# dynext_v1_0.net
KiCad netlist of a schematic drawn in EAGLE
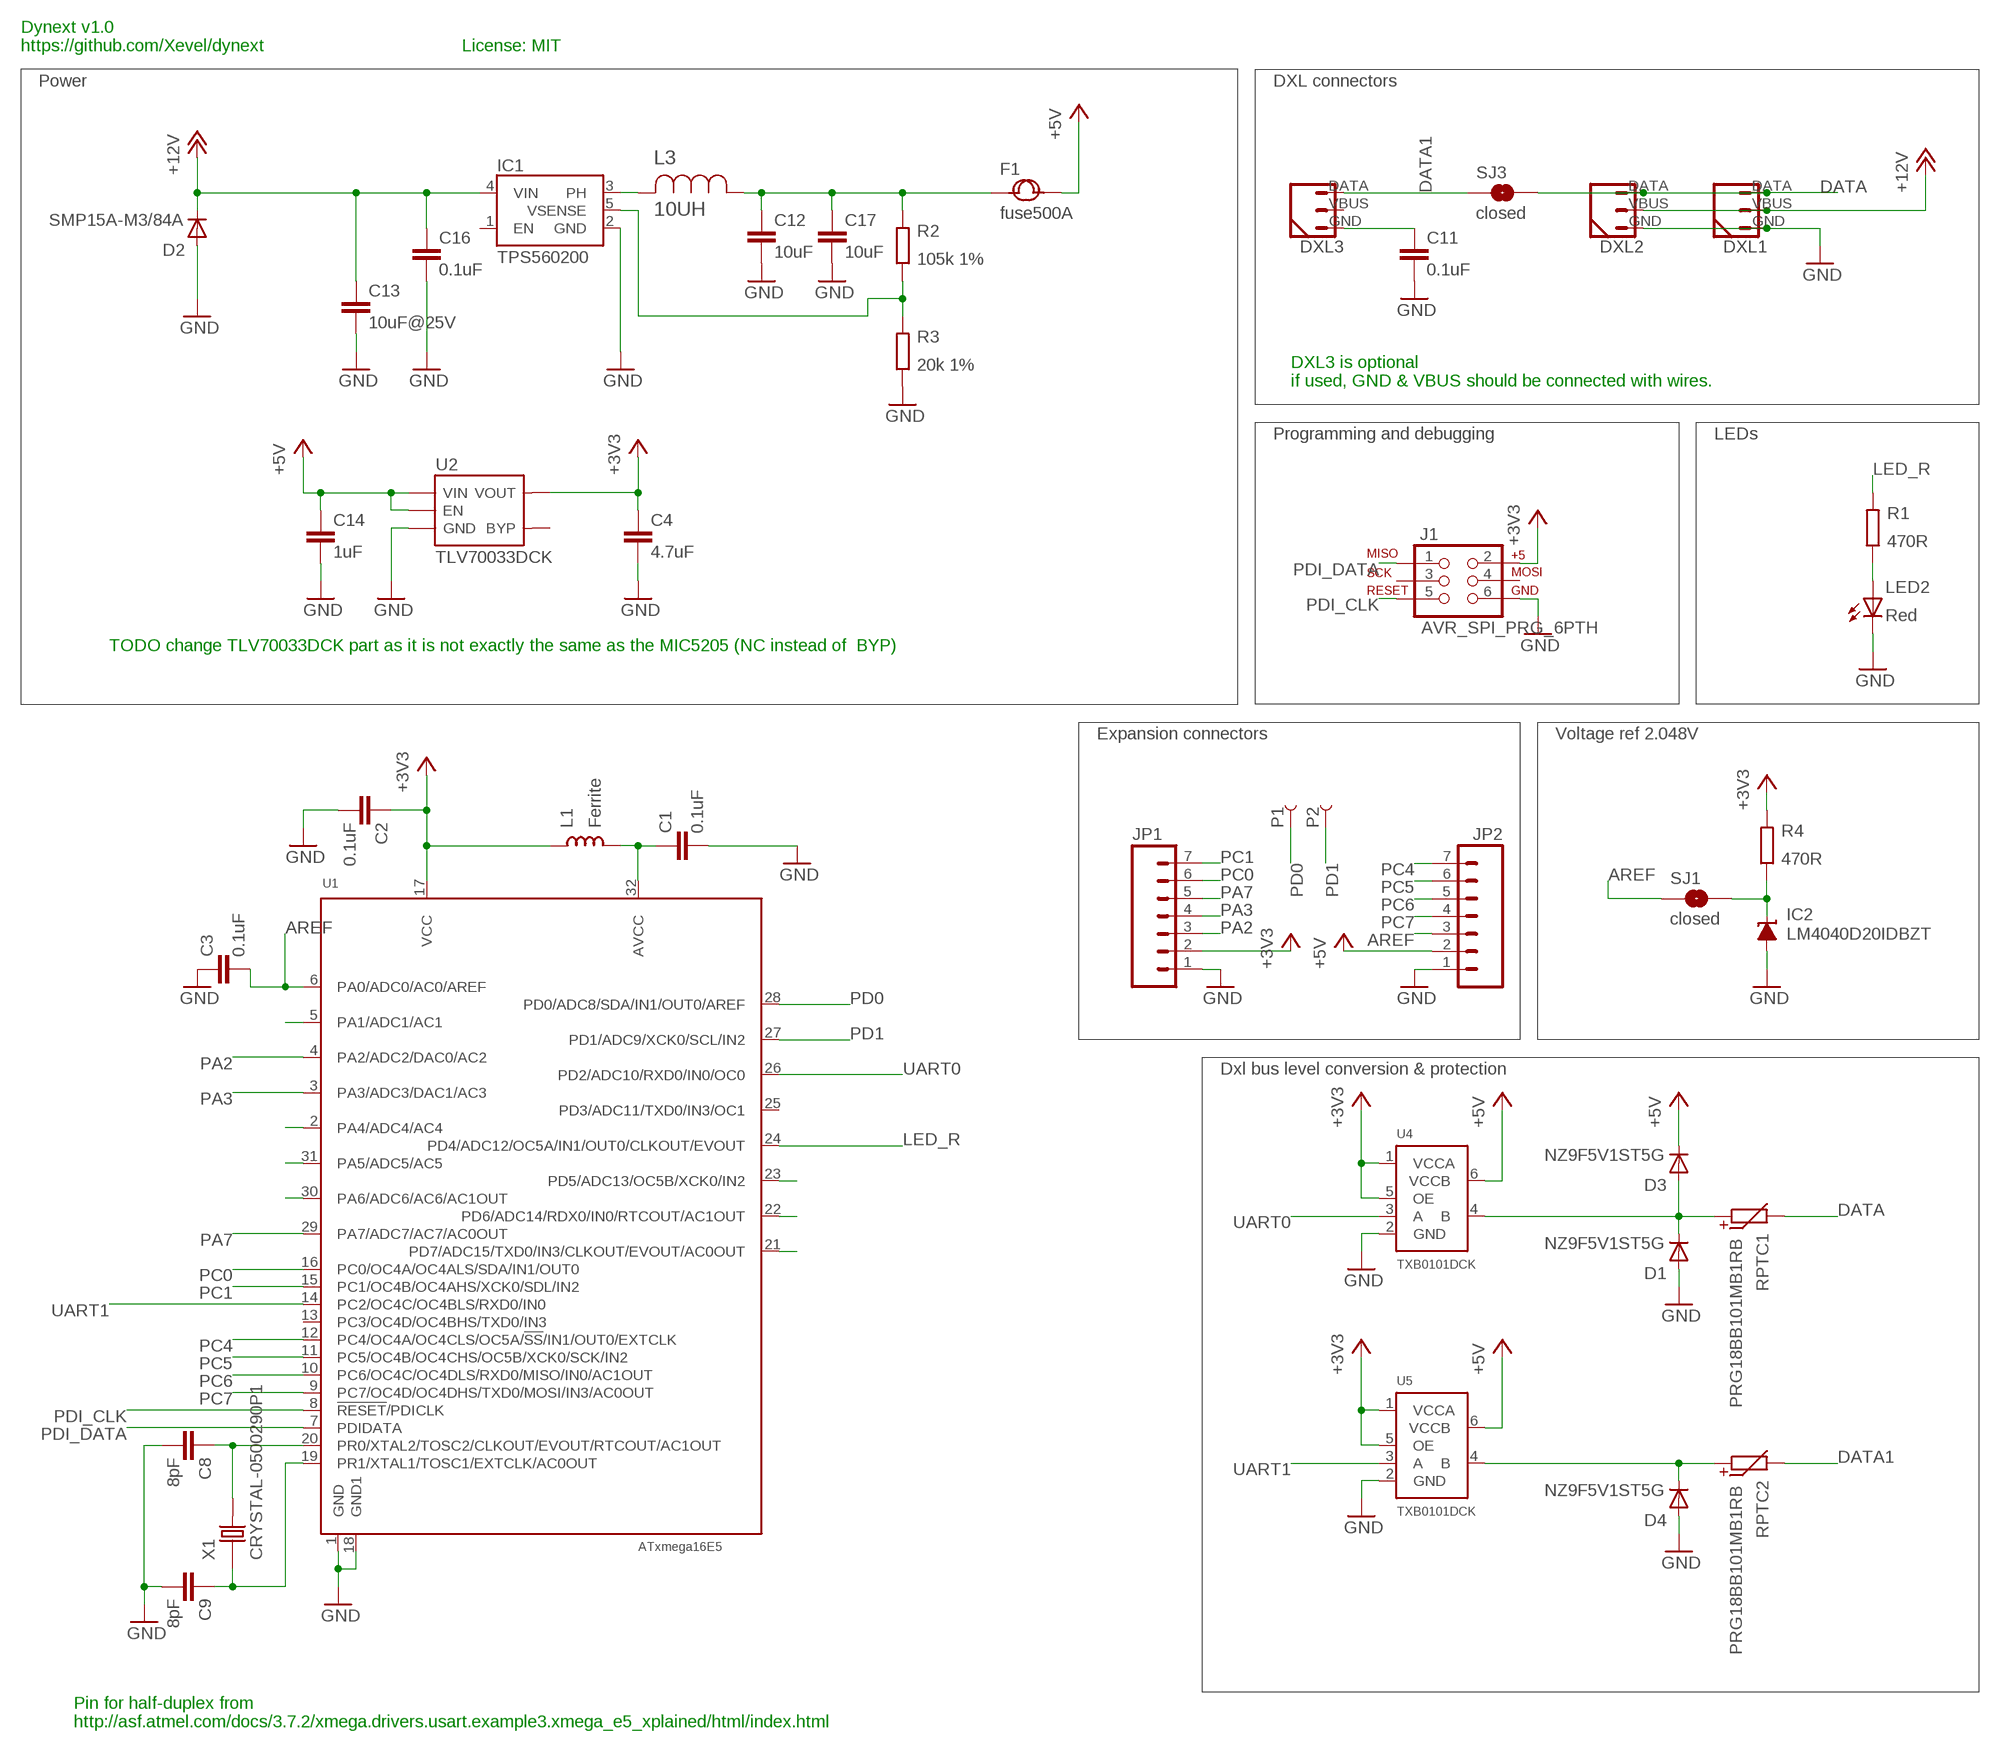
[diagram p0: schematic, sheet 1]

(export (version "E")
  (design (tool "Eeschema 10.0.6"))
  (components
    (comp (ref "C1")
      (value "0.1uF")
      (footprint "eagle-import:0402_N")
      (libsource (lib "eagle-import") (part "C0402"))
    )
    (comp (ref "C2")
      (value "0.1uF")
      (footprint "eagle-import:0402_N")
      (libsource (lib "eagle-import") (part "C0402"))
    )
    (comp (ref "C3")
      (value "0.1uF")
      (footprint "eagle-import:0402_N")
      (libsource (lib "eagle-import") (part "C0402"))
    )
    (comp (ref "C4")
      (value "4.7uF")
      (footprint "eagle-import:0603_N")
      (libsource (lib "eagle-import") (part "C0603"))
    )
    (comp (ref "C8")
      (value "8pF")
      (footprint "eagle-import:0402_N")
      (libsource (lib "eagle-import") (part "C0402"))
    )
    (comp (ref "C9")
      (value "8pF")
      (footprint "eagle-import:0402_N")
      (libsource (lib "eagle-import") (part "C0402"))
    )
    (comp (ref "C11")
      (value "0.1uF")
      (footprint "eagle-import:0402_N")
      (libsource (lib "eagle-import") (part "C0402"))
    )
    (comp (ref "C12")
      (value "10uF")
      (footprint "eagle-import:0805_N")
      (libsource (lib "eagle-import") (part "C0805"))
    )
    (comp (ref "C13")
      (value "10uF@25V")
      (footprint "eagle-import:0805_N")
      (libsource (lib "eagle-import") (part "C0805"))
    )
    (comp (ref "C14")
      (value "1uF")
      (footprint "eagle-import:0402_N")
      (libsource (lib "eagle-import") (part "C0402"))
    )
    (comp (ref "C16")
      (value "0.1uF")
      (footprint "eagle-import:0402_N")
      (libsource (lib "eagle-import") (part "C0402"))
    )
    (comp (ref "C17")
      (value "10uF")
      (footprint "eagle-import:0805_N")
      (libsource (lib "eagle-import") (part "C0805"))
    )
    (comp (ref "D1")
      (value "NZ9F5V1ST5G")
      (footprint "eagle-import:SOD-523_N")
      (libsource (lib "eagle-import") (part "DIODE-SOD523"))
    )
    (comp (ref "D2")
      (value "SMP15A-M3/84A")
      (footprint "eagle-import:DO-220AA")
      (libsource (lib "eagle-import") (part "DIODE-SMP"))
    )
    (comp (ref "D3")
      (value "NZ9F5V1ST5G")
      (footprint "eagle-import:SOD-523_N")
      (libsource (lib "eagle-import") (part "DIODE-SOD523"))
    )
    (comp (ref "D4")
      (value "NZ9F5V1ST5G")
      (footprint "eagle-import:SOD-523_N")
      (libsource (lib "eagle-import") (part "DIODE-SOD523"))
    )
    (comp (ref "DXL1")
      (value "DYNAMIXEL_3POS-T")
      (footprint "eagle-import:DYNAMIXEL_3POS_TOP")
      (libsource (lib "eagle-import") (part "DYNAMIXEL_3POS-T"))
    )
    (comp (ref "DXL2")
      (value "DYNAMIXEL_3POS-T")
      (footprint "eagle-import:DYNAMIXEL_3POS_TOP")
      (libsource (lib "eagle-import") (part "DYNAMIXEL_3POS-T"))
    )
    (comp (ref "DXL3")
      (value "DYNAMIXEL_3POS-R")
      (footprint "eagle-import:DYNAMIXEL_3POS_RIGHT")
      (libsource (lib "eagle-import") (part "DYNAMIXEL_3POS-R"))
    )
    (comp (ref "F1")
      (value "fuse500A")
      (footprint "eagle-import:F1206")
      (libsource (lib "eagle-import") (part "FUSE-1206"))
    )
    (comp (ref "IC1")
      (value "TPS560200")
      (footprint "eagle-import:SOT-23-5_N")
      (libsource (lib "eagle-import") (part "IC_TPS560200"))
    )
    (comp (ref "IC2")
      (value "LM4040D20IDBZT")
      (footprint "eagle-import:DBZ_R-PDSO-G3")
      (fields (field (name "MPN") "LM4041A12IDBZR"))
      (libsource (lib "eagle-import") (part "LM4041DBZA12"))
    )
    (comp (ref "J1")
      (value "AVR_SPI_PRG_6PTH")
      (footprint "eagle-import:2X3")
      (libsource (lib "eagle-import") (part "AVR_SPI_PRG_6PTH"))
    )
    (comp (ref "JP1")
      (value "M07")
      (footprint "eagle-import:1X07")
      (libsource (lib "eagle-import") (part "M07"))
    )
    (comp (ref "JP2")
      (value "M07")
      (footprint "eagle-import:1X07")
      (libsource (lib "eagle-import") (part "M07"))
    )
    (comp (ref "L1")
      (value "Ferrite")
      (footprint "eagle-import:0603_N")
      (libsource (lib "eagle-import") (part "L0603"))
    )
    (comp (ref "L3")
      (value "10UH")
      (footprint "eagle-import:IND_ELL4XG")
      (fields (field (name "MPN") "ELL4LG100MA"))
      (libsource (lib "eagle-import") (part "ELL-4XG4LG100MA"))
    )
    (comp (ref "LED2")
      (value "Red")
      (footprint "eagle-import:D_0603_N")
      (libsource (lib "eagle-import") (part "LED0603"))
    )
    (comp (ref "P1")
      (value "PIN_SMD_2X2.5")
      (footprint "eagle-import:PIN_SMD_2X2.5")
      (libsource (lib "eagle-import") (part "PIN_SMD_2X2.5"))
    )
    (comp (ref "P2")
      (value "PIN_SMD_2X2.5")
      (footprint "eagle-import:PIN_SMD_2X2.5")
      (libsource (lib "eagle-import") (part "PIN_SMD_2X2.5"))
    )
    (comp (ref "R1")
      (value "470R")
      (footprint "eagle-import:0402_N")
      (libsource (lib "eagle-import") (part "R0402"))
    )
    (comp (ref "R2")
      (value "105k 1%")
      (footprint "eagle-import:0402_N")
      (libsource (lib "eagle-import") (part "R0402"))
    )
    (comp (ref "R3")
      (value "20k 1%")
      (footprint "eagle-import:0402_N")
      (libsource (lib "eagle-import") (part "R0402"))
    )
    (comp (ref "R4")
      (value "470R")
      (footprint "eagle-import:0402_N")
      (libsource (lib "eagle-import") (part "R0402"))
    )
    (comp (ref "RPTC1")
      (value "PRG18BB101MB1RB")
      (footprint "eagle-import:0603_N")
      (libsource (lib "eagle-import") (part "R-PTC0603"))
    )
    (comp (ref "RPTC2")
      (value "PRG18BB101MB1RB")
      (footprint "eagle-import:0603_N")
      (libsource (lib "eagle-import") (part "R-PTC0603"))
    )
    (comp (ref "SJ1")
      (value "closed")
      (footprint "eagle-import:SJ_2S-TRACE2")
      (libsource (lib "eagle-import") (part "SOLDERJUMPER2_TRACE2"))
    )
    (comp (ref "SJ3")
      (value "closed")
      (footprint "eagle-import:SJ_2S-TRACE2")
      (libsource (lib "eagle-import") (part "SOLDERJUMPER2_TRACE2"))
    )
    (comp (ref "U1")
      (value "ATxmega16E5")
      (footprint "eagle-import:QFN-32_50P_L_MOD")
      (libsource (lib "eagle-import") (part "ATXMEGAE5-MU_MOD"))
    )
    (comp (ref "U2")
      (value "TLV70033DCK")
      (footprint "eagle-import:SC70-5")
      (libsource (lib "eagle-import") (part "MIC5205-3.3YM5"))
    )
    (comp (ref "U4")
      (value "TXB0101DCK")
      (footprint "eagle-import:SC70-6")
      (libsource (lib "eagle-import") (part "TXB0101DCK"))
    )
    (comp (ref "U5")
      (value "TXB0101DCK")
      (footprint "eagle-import:SC70-6")
      (libsource (lib "eagle-import") (part "TXB0101DCK"))
    )
    (comp (ref "X1")
      (value "CRYSTAL-0500290P1")
      (footprint "eagle-import:2P-SMD-5.0X3.2")
      (libsource (lib "eagle-import") (part "CRYSTAL-0500290P1"))
    )
  )
  (nets
    (net (code "1") (name "+3V3") (class "Default")
      (node (ref "C2") (pin "1") (pinfunction "1_1") (pintype "passive"))
      (node (ref "C4") (pin "1") (pinfunction "1_1") (pintype "passive"))
      (node (ref "J1") (pin "2") (pinfunction "2_2") (pintype "passive"))
      (node (ref "JP1") (pin "2") (pinfunction "2_2") (pintype "passive"))
      (node (ref "L1") (pin "1") (pinfunction "1_1") (pintype "passive"))
      (node (ref "R4") (pin "2") (pinfunction "2_2") (pintype "passive"))
      (node (ref "U1") (pin "17") (pinfunction "VCC_17") (pintype "bidirectional"))
      (node (ref "U2") (pin "5") (pinfunction "VOUT_5") (pintype "bidirectional"))
      (node (ref "U4") (pin "1") (pinfunction "VCCA_1") (pintype "bidirectional"))
      (node (ref "U4") (pin "5") (pinfunction "OE_5") (pintype "bidirectional"))
      (node (ref "U5") (pin "1") (pinfunction "VCCA_1") (pintype "bidirectional"))
      (node (ref "U5") (pin "5") (pinfunction "OE_5") (pintype "bidirectional"))
    )
    (net (code "2") (name "+5V") (class "Default")
      (node (ref "C14") (pin "1") (pinfunction "1_1") (pintype "passive"))
      (node (ref "D3") (pin "C") (pinfunction "C_C") (pintype "passive"))
      (node (ref "F1") (pin "2") (pinfunction "2_2") (pintype "bidirectional"))
      (node (ref "JP2") (pin "2") (pinfunction "2_2") (pintype "passive"))
      (node (ref "U2") (pin "1") (pinfunction "VIN_1") (pintype "bidirectional"))
      (node (ref "U2") (pin "3") (pinfunction "EN_3") (pintype "bidirectional"))
      (node (ref "U4") (pin "6") (pinfunction "VCCB_6") (pintype "bidirectional"))
      (node (ref "U5") (pin "6") (pinfunction "VCCB_6") (pintype "bidirectional"))
    )
    (net (code "3") (name "+12V") (class "Default")
      (node (ref "C13") (pin "1") (pinfunction "1_1") (pintype "passive"))
      (node (ref "C16") (pin "1") (pinfunction "1_1") (pintype "passive"))
      (node (ref "D2") (pin "C") (pinfunction "C_C") (pintype "passive"))
      (node (ref "DXL1") (pin "VBUS") (pinfunction "2_VBUS") (pintype "bidirectional"))
      (node (ref "DXL2") (pin "VBUS") (pinfunction "2_VBUS") (pintype "bidirectional"))
      (node (ref "IC1") (pin "4") (pinfunction "VIN_4") (pintype "bidirectional"))
    )
    (net (code "4") (name "/AREF") (class "Default")
      (node (ref "C3") (pin "2") (pinfunction "2_2") (pintype "passive"))
      (node (ref "JP2") (pin "3") (pinfunction "3_3") (pintype "passive"))
      (node (ref "SJ1") (pin "1") (pinfunction "1_1") (pintype "passive"))
      (node (ref "U1") (pin "6") (pinfunction "PA0/ADC0/AC0/AREF_6") (pintype "bidirectional"))
    )
    (net (code "5") (name "/DATA") (class "Default")
      (node (ref "DXL1") (pin "DATA") (pinfunction "3_DATA") (pintype "bidirectional"))
      (node (ref "DXL2") (pin "DATA") (pinfunction "3_DATA") (pintype "bidirectional"))
      (node (ref "RPTC1") (pin "2") (pinfunction "2_2") (pintype "passive"))
      (node (ref "SJ3") (pin "2") (pinfunction "2_2") (pintype "passive"))
    )
    (net (code "6") (name "/DATA1") (class "Default")
      (node (ref "DXL3") (pin "DATA") (pinfunction "3_DATA") (pintype "bidirectional"))
      (node (ref "RPTC2") (pin "2") (pinfunction "2_2") (pintype "passive"))
      (node (ref "SJ3") (pin "1") (pinfunction "1_1") (pintype "passive"))
    )
    (net (code "7") (name "/LED_R") (class "Default")
      (node (ref "R1") (pin "2") (pinfunction "2_2") (pintype "passive"))
      (node (ref "U1") (pin "24") (pinfunction "PD4/ADC12/OC5A/IN1/OUT0/CLKOUT/EVOUT_24") (pintype "bidirectional"))
    )
    (net (code "8") (name "/PA2") (class "Default")
      (node (ref "JP1") (pin "3") (pinfunction "3_3") (pintype "passive"))
      (node (ref "U1") (pin "4") (pinfunction "PA2/ADC2/DAC0/AC2_4") (pintype "bidirectional"))
    )
    (net (code "9") (name "/PA3") (class "Default")
      (node (ref "JP1") (pin "4") (pinfunction "4_4") (pintype "passive"))
      (node (ref "U1") (pin "3") (pinfunction "PA3/ADC3/DAC1/AC3_3") (pintype "bidirectional"))
    )
    (net (code "10") (name "/PA7") (class "Default")
      (node (ref "JP1") (pin "5") (pinfunction "5_5") (pintype "passive"))
      (node (ref "U1") (pin "29") (pinfunction "PA7/ADC7/AC7/AC0OUT_29") (pintype "bidirectional"))
    )
    (net (code "11") (name "/PC0") (class "Default")
      (node (ref "JP1") (pin "6") (pinfunction "6_6") (pintype "passive"))
      (node (ref "U1") (pin "16") (pinfunction "PC0/OC4A/OC4ALS/SDA/IN1/OUT0_16") (pintype "bidirectional"))
    )
    (net (code "12") (name "/PC1") (class "Default")
      (node (ref "JP1") (pin "7") (pinfunction "7_7") (pintype "passive"))
      (node (ref "U1") (pin "15") (pinfunction "PC1/OC4B/OC4AHS/XCK0/SDL/IN2_15") (pintype "bidirectional"))
    )
    (net (code "13") (name "/PC4") (class "Default")
      (node (ref "JP2") (pin "7") (pinfunction "7_7") (pintype "passive"))
      (node (ref "U1") (pin "12") (pinfunction "PC4/OC4A/OC4CLS/OC5A/~{SS}/IN1/OUT0/EXTCLK_12") (pintype "bidirectional"))
    )
    (net (code "14") (name "/PC5") (class "Default")
      (node (ref "JP2") (pin "6") (pinfunction "6_6") (pintype "passive"))
      (node (ref "U1") (pin "11") (pinfunction "PC5/OC4B/OC4CHS/OC5B/XCK0/SCK/IN2_11") (pintype "bidirectional"))
    )
    (net (code "15") (name "/PC6") (class "Default")
      (node (ref "JP2") (pin "5") (pinfunction "5_5") (pintype "passive"))
      (node (ref "U1") (pin "10") (pinfunction "PC6/OC4C/OC4DLS/RXD0/MISO/IN0/AC1OUT_10") (pintype "bidirectional"))
    )
    (net (code "16") (name "/PC7") (class "Default")
      (node (ref "JP2") (pin "4") (pinfunction "4_4") (pintype "passive"))
      (node (ref "U1") (pin "9") (pinfunction "PC7/OC4D/OC4DHS/TXD0/MOSI/IN3/AC0OUT_9") (pintype "bidirectional"))
    )
    (net (code "17") (name "/PD0") (class "Default")
      (node (ref "P1") (pin "PIN") (pinfunction "1_PIN") (pintype "bidirectional"))
      (node (ref "U1") (pin "28") (pinfunction "PD0/ADC8/SDA/IN1/OUT0/AREF_28") (pintype "bidirectional"))
    )
    (net (code "18") (name "/PD1") (class "Default")
      (node (ref "P2") (pin "PIN") (pinfunction "1_PIN") (pintype "bidirectional"))
      (node (ref "U1") (pin "27") (pinfunction "PD1/ADC9/XCK0/SCL/IN2_27") (pintype "bidirectional"))
    )
    (net (code "19") (name "/PDI_CLK") (class "Default")
      (node (ref "J1") (pin "5") (pinfunction "5_5") (pintype "passive"))
      (node (ref "U1") (pin "8") (pinfunction "~{RESET}/PDICLK_8") (pintype "bidirectional"))
    )
    (net (code "20") (name "/PDI_DATA") (class "Default")
      (node (ref "J1") (pin "1") (pinfunction "1_1") (pintype "passive"))
      (node (ref "U1") (pin "7") (pinfunction "PDIDATA_7") (pintype "bidirectional"))
    )
    (net (code "21") (name "/UART0") (class "Default")
      (node (ref "U1") (pin "26") (pinfunction "PD2/ADC10/RXD0/IN0/OC0_26") (pintype "bidirectional"))
      (node (ref "U4") (pin "3") (pinfunction "A_3") (pintype "bidirectional"))
    )
    (net (code "22") (name "/UART1") (class "Default")
      (node (ref "U1") (pin "14") (pinfunction "PC2/OC4C/OC4BLS/RXD0/IN0_14") (pintype "bidirectional"))
      (node (ref "U5") (pin "3") (pinfunction "A_3") (pintype "bidirectional"))
    )
    (net (code "23") (name "GND") (class "Default")
      (node (ref "C1") (pin "2") (pinfunction "2_2") (pintype "passive"))
      (node (ref "C11") (pin "2") (pinfunction "2_2") (pintype "passive"))
      (node (ref "C12") (pin "2") (pinfunction "2_2") (pintype "passive"))
      (node (ref "C13") (pin "2") (pinfunction "2_2") (pintype "passive"))
      (node (ref "C14") (pin "2") (pinfunction "2_2") (pintype "passive"))
      (node (ref "C16") (pin "2") (pinfunction "2_2") (pintype "passive"))
      (node (ref "C17") (pin "2") (pinfunction "2_2") (pintype "passive"))
      (node (ref "C2") (pin "2") (pinfunction "2_2") (pintype "passive"))
      (node (ref "C3") (pin "1") (pinfunction "1_1") (pintype "passive"))
      (node (ref "C4") (pin "2") (pinfunction "2_2") (pintype "passive"))
      (node (ref "C8") (pin "2") (pinfunction "2_2") (pintype "passive"))
      (node (ref "C9") (pin "2") (pinfunction "2_2") (pintype "passive"))
      (node (ref "D1") (pin "A") (pinfunction "A_A") (pintype "passive"))
      (node (ref "D2") (pin "A") (pinfunction "A_A") (pintype "passive"))
      (node (ref "D4") (pin "A") (pinfunction "A_A") (pintype "passive"))
      (node (ref "DXL1") (pin "GND") (pinfunction "1_GND") (pintype "bidirectional"))
      (node (ref "DXL2") (pin "GND") (pinfunction "1_GND") (pintype "bidirectional"))
      (node (ref "IC1") (pin "2") (pinfunction "GND_2") (pintype "input"))
      (node (ref "IC2") (pin "2") (pinfunction "A_2") (pintype "passive"))
      (node (ref "J1") (pin "6") (pinfunction "6_6") (pintype "passive"))
      (node (ref "JP1") (pin "1") (pinfunction "1_1") (pintype "passive"))
      (node (ref "JP2") (pin "1") (pinfunction "1_1") (pintype "passive"))
      (node (ref "LED2") (pin "C") (pinfunction "C_C") (pintype "passive"))
      (node (ref "R3") (pin "1") (pinfunction "1_1") (pintype "passive"))
      (node (ref "U1") (pin "1") (pinfunction "GND_1") (pintype "bidirectional"))
      (node (ref "U1") (pin "18") (pinfunction "GND1_18") (pintype "bidirectional"))
      (node (ref "U2") (pin "2") (pinfunction "GND_2") (pintype "bidirectional"))
      (node (ref "U4") (pin "2") (pinfunction "GND_2") (pintype "bidirectional"))
      (node (ref "U5") (pin "2") (pinfunction "GND_2") (pintype "bidirectional"))
    )
    (net (code "24") (name "Net-(C12-Pad1)") (class "Default")
      (node (ref "C12") (pin "1") (pinfunction "1_1") (pintype "passive"))
      (node (ref "C17") (pin "1") (pinfunction "1_1") (pintype "passive"))
      (node (ref "F1") (pin "1") (pinfunction "1_1") (pintype "bidirectional"))
      (node (ref "L3") (pin "1") (pinfunction "1_1") (pintype "passive"))
      (node (ref "R2") (pin "2") (pinfunction "2_2") (pintype "passive"))
    )
    (net (code "25") (name "Net-(DXL3-1)") (class "Default")
      (node (ref "C11") (pin "1") (pinfunction "1_1") (pintype "passive"))
      (node (ref "DXL3") (pin "GND") (pinfunction "1_GND") (pintype "bidirectional"))
    )
    (net (code "26") (name "Net-(IC1-PH)") (class "Default")
      (node (ref "IC1") (pin "3") (pinfunction "PH_3") (pintype "bidirectional"))
      (node (ref "L3") (pin "2") (pinfunction "2_2") (pintype "passive"))
    )
    (net (code "27") (name "Net-(IC1-VSENSE)") (class "Default")
      (node (ref "IC1") (pin "5") (pinfunction "VSENSE_5") (pintype "bidirectional"))
      (node (ref "R2") (pin "1") (pinfunction "1_1") (pintype "passive"))
      (node (ref "R3") (pin "2") (pinfunction "2_2") (pintype "passive"))
    )
    (net (code "28") (name "Net-(IC2-C)") (class "Default")
      (node (ref "IC2") (pin "1") (pinfunction "C_1") (pintype "passive"))
      (node (ref "R4") (pin "1") (pinfunction "1_1") (pintype "passive"))
      (node (ref "SJ1") (pin "2") (pinfunction "2_2") (pintype "passive"))
    )
    (net (code "29") (name "Net-(LED2-PadA)") (class "Default")
      (node (ref "LED2") (pin "A") (pinfunction "A_A") (pintype "passive"))
      (node (ref "R1") (pin "1") (pinfunction "1_1") (pintype "passive"))
    )
    (net (code "30") (name "Net-(U1-AVCC)") (class "Default")
      (node (ref "C1") (pin "1") (pinfunction "1_1") (pintype "passive"))
      (node (ref "L1") (pin "2") (pinfunction "2_2") (pintype "passive"))
      (node (ref "U1") (pin "32") (pinfunction "AVCC_32") (pintype "bidirectional"))
    )
    (net (code "31") (name "Net-(U1-PR0{slash}XTAL2{slash}TOSC2{slash}CLKOUT{slash}EVOUT{slash}RTCOUT{slash}AC1OUT)") (class "Default")
      (node (ref "C8") (pin "1") (pinfunction "1_1") (pintype "passive"))
      (node (ref "U1") (pin "20") (pinfunction "PR0/XTAL2/TOSC2/CLKOUT/EVOUT/RTCOUT/AC1OUT_20") (pintype "bidirectional"))
      (node (ref "X1") (pin "2") (pinfunction "2_2") (pintype "passive"))
    )
    (net (code "32") (name "Net-(U1-PR1{slash}XTAL1{slash}TOSC1{slash}EXTCLK{slash}AC0OUT)") (class "Default")
      (node (ref "C9") (pin "1") (pinfunction "1_1") (pintype "passive"))
      (node (ref "U1") (pin "19") (pinfunction "PR1/XTAL1/TOSC1/EXTCLK/AC0OUT_19") (pintype "bidirectional"))
      (node (ref "X1") (pin "1") (pinfunction "1_1") (pintype "passive"))
    )
    (net (code "33") (name "Net-(U4-B)") (class "Default")
      (node (ref "D1") (pin "C") (pinfunction "C_C") (pintype "passive"))
      (node (ref "D3") (pin "A") (pinfunction "A_A") (pintype "passive"))
      (node (ref "RPTC1") (pin "1") (pinfunction "1_1") (pintype "passive"))
      (node (ref "U4") (pin "4") (pinfunction "B_4") (pintype "bidirectional"))
    )
    (net (code "34") (name "Net-(U5-B)") (class "Default")
      (node (ref "D4") (pin "C") (pinfunction "C_C") (pintype "passive"))
      (node (ref "RPTC2") (pin "1") (pinfunction "1_1") (pintype "passive"))
      (node (ref "U5") (pin "4") (pinfunction "B_4") (pintype "bidirectional"))
    )
    (net (code "35") (name "unconnected-(DXL3-2-PadVBUS)") (class "Default")
      (node (ref "DXL3") (pin "VBUS") (pinfunction "2_VBUS") (pintype "bidirectional"))
    )
    (net (code "36") (name "unconnected-(IC1-EN-Pad1)") (class "Default")
      (node (ref "IC1") (pin "1") (pinfunction "EN_1") (pintype "input"))
    )
    (net (code "37") (name "unconnected-(J1-Pad3)") (class "Default")
      (node (ref "J1") (pin "3") (pinfunction "3_3") (pintype "passive"))
    )
    (net (code "38") (name "unconnected-(J1-Pad4)") (class "Default")
      (node (ref "J1") (pin "4") (pinfunction "4_4") (pintype "passive"))
    )
    (net (code "39") (name "unconnected-(U1-PA1{slash}ADC1{slash}AC1-Pad5)") (class "Default")
      (node (ref "U1") (pin "5") (pinfunction "PA1/ADC1/AC1_5") (pintype "bidirectional"))
    )
    (net (code "40") (name "unconnected-(U1-PA4{slash}ADC4{slash}AC4-Pad2)") (class "Default")
      (node (ref "U1") (pin "2") (pinfunction "PA4/ADC4/AC4_2") (pintype "bidirectional"))
    )
    (net (code "41") (name "unconnected-(U1-PA5{slash}ADC5{slash}AC5-Pad31)") (class "Default")
      (node (ref "U1") (pin "31") (pinfunction "PA5/ADC5/AC5_31") (pintype "bidirectional"))
    )
    (net (code "42") (name "unconnected-(U1-PA6{slash}ADC6{slash}AC6{slash}AC1OUT-Pad30)") (class "Default")
      (node (ref "U1") (pin "30") (pinfunction "PA6/ADC6/AC6/AC1OUT_30") (pintype "bidirectional"))
    )
    (net (code "43") (name "unconnected-(U1-PC3{slash}OC4D{slash}OC4BHS{slash}TXD0{slash}IN3-Pad13)") (class "Default")
      (node (ref "U1") (pin "13") (pinfunction "PC3/OC4D/OC4BHS/TXD0/IN3_13") (pintype "bidirectional"))
    )
    (net (code "44") (name "unconnected-(U1-PD3{slash}ADC11{slash}TXD0{slash}IN3{slash}OC1-Pad25)") (class "Default")
      (node (ref "U1") (pin "25") (pinfunction "PD3/ADC11/TXD0/IN3/OC1_25") (pintype "bidirectional"))
    )
    (net (code "45") (name "unconnected-(U1-PD5{slash}ADC13{slash}OC5B{slash}XCK0{slash}IN2-Pad23)") (class "Default")
      (node (ref "U1") (pin "23") (pinfunction "PD5/ADC13/OC5B/XCK0/IN2_23") (pintype "bidirectional"))
    )
    (net (code "46") (name "unconnected-(U1-PD6{slash}ADC14{slash}RDX0{slash}IN0{slash}RTCOUT{slash}AC1OUT-Pad22)") (class "Default")
      (node (ref "U1") (pin "22") (pinfunction "PD6/ADC14/RDX0/IN0/RTCOUT/AC1OUT_22") (pintype "bidirectional"))
    )
    (net (code "47") (name "unconnected-(U1-PD7{slash}ADC15{slash}TXD0{slash}IN3{slash}CLKOUT{slash}EVOUT{slash}AC0OUT-Pad21)") (class "Default")
      (node (ref "U1") (pin "21") (pinfunction "PD7/ADC15/TXD0/IN3/CLKOUT/EVOUT/AC0OUT_21") (pintype "bidirectional"))
    )
    (net (code "48") (name "unconnected-(U2-BYP-Pad4)") (class "Default")
      (node (ref "U2") (pin "4") (pinfunction "BYP_4") (pintype "bidirectional"))
    )
  )
)
